# PixelShirtConsole.net
KiCad netlist of a schematic drawn in EAGLE
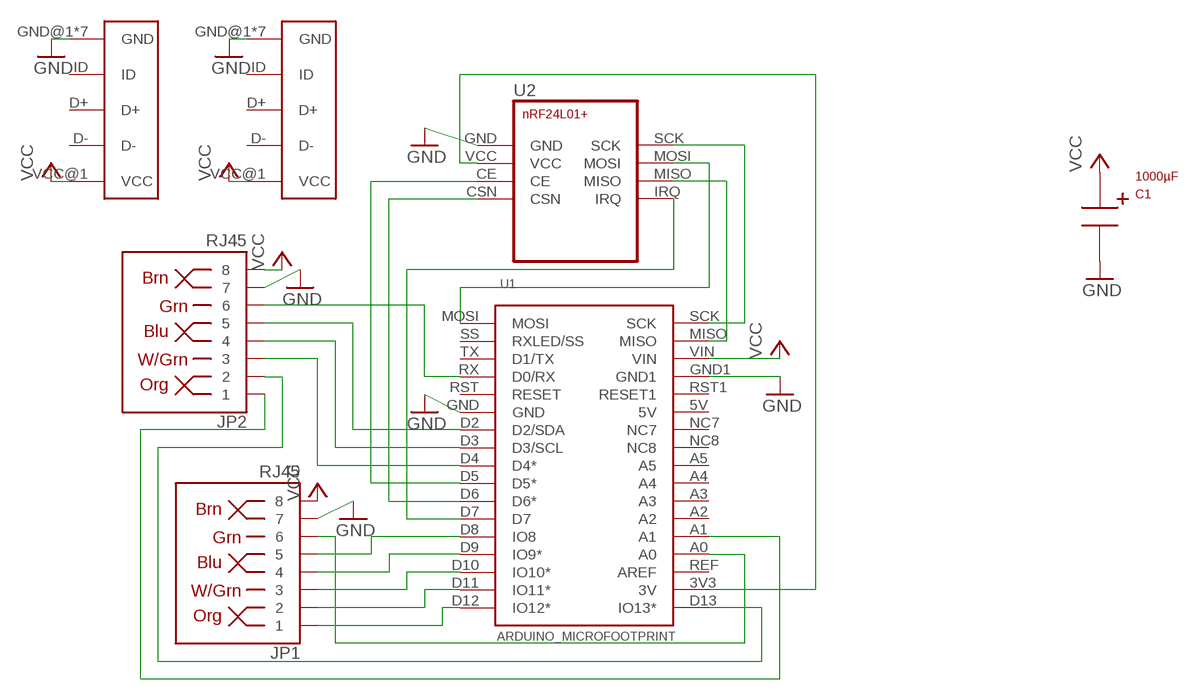
[diagram p0: schematic, sheet 1]

(export (version "E")
  (design (tool "Eeschema 10.0.6"))
  (components
    (comp (ref "C1")
      (value "1000µF")
      (footprint "eagle-import:CAP-CUSTOM")
      (libsource (lib "eagle-import") (part "CAP-CUSTOM"))
    )
    (comp (ref "JP1")
      (value "RJ45")
      (footprint "eagle-import:RJ45-8")
      (libsource (lib "eagle-import") (part "RJ45-8PTH"))
    )
    (comp (ref "JP2")
      (value "RJ45")
      (footprint "eagle-import:RJ45-8")
      (libsource (lib "eagle-import") (part "RJ45-8PTH"))
    )
    (comp (ref "JP3")
      (value "USB-MICRO-B")
      (footprint "eagle-import:USB-MICRO-B")
      (libsource (lib "eagle-import") (part "USB-MICRO-B"))
    )
    (comp (ref "JP4")
      (value "USB-MICRO-B")
      (footprint "eagle-import:USB-MICRO-B")
      (libsource (lib "eagle-import") (part "USB-MICRO-B"))
    )
    (comp (ref "U1")
      (value "ARDUINO_MICROFOOTPRINT")
      (footprint "eagle-import:ARDUINO-MICRO")
      (libsource (lib "eagle-import") (part "ARDUINO_MICROFOOTPRINT"))
    )
    (comp (ref "U2")
      (value "NRF24L01+")
      (footprint "eagle-import:NRF24L01+")
      (libsource (lib "eagle-import") (part "NRF24L01+"))
    )
  )
  (nets
    (net (code "1") (name "GND") (class "Default")
      (node (ref "C1") (pin "GND") (pinfunction "GND_GND") (pintype "bidirectional"))
      (node (ref "JP1") (pin "7") (pinfunction "7_7") (pintype "bidirectional"))
      (node (ref "JP2") (pin "7") (pinfunction "7_7") (pintype "bidirectional"))
      (node (ref "JP3") (pin "GND@1") (pinfunction "GND_GND@1") (pintype "bidirectional"))
      (node (ref "JP3") (pin "GND@2") (pinfunction "GND_GND@2") (pintype "bidirectional"))
      (node (ref "JP3") (pin "GND@3") (pinfunction "GND_GND@3") (pintype "bidirectional"))
      (node (ref "JP3") (pin "GND@5") (pinfunction "GND_GND@5") (pintype "bidirectional"))
      (node (ref "JP3") (pin "GND@6") (pinfunction "GND_GND@6") (pintype "bidirectional"))
      (node (ref "JP3") (pin "GND@7") (pinfunction "GND_GND@7") (pintype "bidirectional"))
      (node (ref "JP3") (pin "GNF@4") (pinfunction "GND_GNF@4") (pintype "bidirectional"))
      (node (ref "JP4") (pin "GND@1") (pinfunction "GND_GND@1") (pintype "bidirectional"))
      (node (ref "JP4") (pin "GND@2") (pinfunction "GND_GND@2") (pintype "bidirectional"))
      (node (ref "JP4") (pin "GND@3") (pinfunction "GND_GND@3") (pintype "bidirectional"))
      (node (ref "JP4") (pin "GND@5") (pinfunction "GND_GND@5") (pintype "bidirectional"))
      (node (ref "JP4") (pin "GND@6") (pinfunction "GND_GND@6") (pintype "bidirectional"))
      (node (ref "JP4") (pin "GND@7") (pinfunction "GND_GND@7") (pintype "bidirectional"))
      (node (ref "JP4") (pin "GNF@4") (pinfunction "GND_GNF@4") (pintype "bidirectional"))
      (node (ref "U1") (pin "GND") (pinfunction "GND_GND") (pintype "bidirectional"))
      (node (ref "U1") (pin "GND1") (pinfunction "GND1_GND1") (pintype "bidirectional"))
      (node (ref "U2") (pin "GND") (pinfunction "GND_GND") (pintype "power_in"))
    )
    (net (code "2") (name "Net-(JP1-Pad6)") (class "Default")
      (node (ref "JP1") (pin "6") (pinfunction "6_6") (pintype "bidirectional"))
      (node (ref "U1") (pin "A0") (pinfunction "A0_A0") (pintype "bidirectional"))
    )
    (net (code "3") (name "Net-(JP2-Pad1)") (class "Default")
      (node (ref "JP2") (pin "1") (pinfunction "1_1") (pintype "bidirectional"))
      (node (ref "U1") (pin "A1") (pinfunction "A1_A1") (pintype "bidirectional"))
    )
    (net (code "4") (name "Net-(U1-3V)") (class "Default")
      (node (ref "U1") (pin "3V3") (pinfunction "3V_3V3") (pintype "bidirectional"))
      (node (ref "U2") (pin "VCC") (pinfunction "VCC_VCC") (pintype "power_in"))
    )
    (net (code "5") (name "Net-(U1-D0{slash}RX)") (class "Default")
      (node (ref "JP2") (pin "6") (pinfunction "6_6") (pintype "bidirectional"))
      (node (ref "U1") (pin "RX") (pinfunction "D0/RX_RX") (pintype "bidirectional"))
    )
    (net (code "6") (name "Net-(U1-D2{slash}SDA)") (class "Default")
      (node (ref "JP2") (pin "5") (pinfunction "5_5") (pintype "bidirectional"))
      (node (ref "U1") (pin "D2") (pinfunction "D2/SDA_D2") (pintype "bidirectional"))
    )
    (net (code "7") (name "Net-(U1-D3{slash}SCL)") (class "Default")
      (node (ref "JP2") (pin "4") (pinfunction "4_4") (pintype "bidirectional"))
      (node (ref "U1") (pin "D3") (pinfunction "D3/SCL_D3") (pintype "bidirectional"))
    )
    (net (code "8") (name "Net-(U1-D4*)") (class "Default")
      (node (ref "JP2") (pin "3") (pinfunction "3_3") (pintype "bidirectional"))
      (node (ref "U1") (pin "D4") (pinfunction "D4*_D4") (pintype "bidirectional"))
    )
    (net (code "9") (name "Net-(U1-D5*)") (class "Default")
      (node (ref "U1") (pin "D5") (pinfunction "D5*_D5") (pintype "bidirectional"))
      (node (ref "U2") (pin "CE") (pinfunction "CE_CE") (pintype "bidirectional"))
    )
    (net (code "10") (name "Net-(U1-D6*)") (class "Default")
      (node (ref "U1") (pin "D6") (pinfunction "D6*_D6") (pintype "bidirectional"))
      (node (ref "U2") (pin "CSN") (pinfunction "CSN_CSN") (pintype "bidirectional"))
    )
    (net (code "11") (name "Net-(U1-IO8)") (class "Default")
      (node (ref "JP1") (pin "5") (pinfunction "5_5") (pintype "bidirectional"))
      (node (ref "U1") (pin "D8") (pinfunction "IO8_D8") (pintype "bidirectional"))
    )
    (net (code "12") (name "Net-(U1-IO9*)") (class "Default")
      (node (ref "JP1") (pin "4") (pinfunction "4_4") (pintype "bidirectional"))
      (node (ref "U1") (pin "D9") (pinfunction "IO9*_D9") (pintype "bidirectional"))
    )
    (net (code "13") (name "Net-(U1-IO10*)") (class "Default")
      (node (ref "JP1") (pin "3") (pinfunction "3_3") (pintype "bidirectional"))
      (node (ref "U1") (pin "D10") (pinfunction "IO10*_D10") (pintype "bidirectional"))
    )
    (net (code "14") (name "Net-(U1-IO11*)") (class "Default")
      (node (ref "JP1") (pin "2") (pinfunction "2_2") (pintype "bidirectional"))
      (node (ref "U1") (pin "D11") (pinfunction "IO11*_D11") (pintype "bidirectional"))
    )
    (net (code "15") (name "Net-(U1-IO12*)") (class "Default")
      (node (ref "JP1") (pin "1") (pinfunction "1_1") (pintype "bidirectional"))
      (node (ref "U1") (pin "D12") (pinfunction "IO12*_D12") (pintype "bidirectional"))
    )
    (net (code "16") (name "Net-(U1-IO13*)") (class "Default")
      (node (ref "JP2") (pin "2") (pinfunction "2_2") (pintype "bidirectional"))
      (node (ref "U1") (pin "D13") (pinfunction "IO13*_D13") (pintype "bidirectional"))
    )
    (net (code "17") (name "Net-(U1-PadD7)") (class "Default")
      (node (ref "U1") (pin "D7") (pinfunction "D7_D7") (pintype "bidirectional"))
      (node (ref "U2") (pin "IRQ") (pinfunction "IRQ_IRQ") (pintype "bidirectional"))
    )
    (net (code "18") (name "Net-(U1-PadMISO)") (class "Default")
      (node (ref "U1") (pin "MISO") (pinfunction "MISO_MISO") (pintype "bidirectional"))
      (node (ref "U2") (pin "MISO") (pinfunction "MISO_MISO") (pintype "bidirectional"))
    )
    (net (code "19") (name "Net-(U1-PadMOSI)") (class "Default")
      (node (ref "U1") (pin "MOSI") (pinfunction "MOSI_MOSI") (pintype "bidirectional"))
      (node (ref "U2") (pin "MOSI") (pinfunction "MOSI_MOSI") (pintype "bidirectional"))
    )
    (net (code "20") (name "Net-(U1-PadSCK)") (class "Default")
      (node (ref "U1") (pin "SCK") (pinfunction "SCK_SCK") (pintype "bidirectional"))
      (node (ref "U2") (pin "SCK") (pinfunction "SCK_SCK") (pintype "bidirectional"))
    )
    (net (code "21") (name "VCC") (class "Default")
      (node (ref "C1") (pin "VCC") (pinfunction "VCC_VCC") (pintype "bidirectional"))
      (node (ref "JP1") (pin "8") (pinfunction "8_8") (pintype "bidirectional"))
      (node (ref "JP2") (pin "8") (pinfunction "8_8") (pintype "bidirectional"))
      (node (ref "JP3") (pin "VCC@1") (pinfunction "VCC_VCC@1") (pintype "bidirectional"))
      (node (ref "JP4") (pin "VCC@1") (pinfunction "VCC_VCC@1") (pintype "bidirectional"))
      (node (ref "U1") (pin "VIN") (pinfunction "VIN_VIN") (pintype "bidirectional"))
    )
    (net (code "22") (name "unconnected-(JP3-PadD+)") (class "Default")
      (node (ref "JP3") (pin "D+") (pinfunction "D+_D+") (pintype "bidirectional"))
    )
    (net (code "23") (name "unconnected-(JP3-PadD-)") (class "Default")
      (node (ref "JP3") (pin "D-") (pinfunction "D-_D-") (pintype "bidirectional"))
    )
    (net (code "24") (name "unconnected-(JP3-PadID)") (class "Default")
      (node (ref "JP3") (pin "ID") (pinfunction "ID_ID") (pintype "bidirectional"))
    )
    (net (code "25") (name "unconnected-(JP4-PadD+)") (class "Default")
      (node (ref "JP4") (pin "D+") (pinfunction "D+_D+") (pintype "bidirectional"))
    )
    (net (code "26") (name "unconnected-(JP4-PadD-)") (class "Default")
      (node (ref "JP4") (pin "D-") (pinfunction "D-_D-") (pintype "bidirectional"))
    )
    (net (code "27") (name "unconnected-(JP4-PadID)") (class "Default")
      (node (ref "JP4") (pin "ID") (pinfunction "ID_ID") (pintype "bidirectional"))
    )
    (net (code "28") (name "unconnected-(U1-AREF-PadREF)") (class "Default")
      (node (ref "U1") (pin "REF") (pinfunction "AREF_REF") (pintype "bidirectional"))
    )
    (net (code "29") (name "unconnected-(U1-D1{slash}TX-PadTX)") (class "Default")
      (node (ref "U1") (pin "TX") (pinfunction "D1/TX_TX") (pintype "bidirectional"))
    )
    (net (code "30") (name "unconnected-(U1-Pad5V)") (class "Default")
      (node (ref "U1") (pin "5V") (pinfunction "5V_5V") (pintype "bidirectional"))
    )
    (net (code "31") (name "unconnected-(U1-PadA2)") (class "Default")
      (node (ref "U1") (pin "A2") (pinfunction "A2_A2") (pintype "bidirectional"))
    )
    (net (code "32") (name "unconnected-(U1-PadA3)") (class "Default")
      (node (ref "U1") (pin "A3") (pinfunction "A3_A3") (pintype "bidirectional"))
    )
    (net (code "33") (name "unconnected-(U1-PadA4)") (class "Default")
      (node (ref "U1") (pin "A4") (pinfunction "A4_A4") (pintype "bidirectional"))
    )
    (net (code "34") (name "unconnected-(U1-PadA5)") (class "Default")
      (node (ref "U1") (pin "A5") (pinfunction "A5_A5") (pintype "bidirectional"))
    )
    (net (code "35") (name "unconnected-(U1-PadNC7)") (class "Default")
      (node (ref "U1") (pin "NC7") (pinfunction "NC7_NC7") (pintype "bidirectional"))
    )
    (net (code "36") (name "unconnected-(U1-PadNC8)") (class "Default")
      (node (ref "U1") (pin "NC8") (pinfunction "NC8_NC8") (pintype "bidirectional"))
    )
    (net (code "37") (name "unconnected-(U1-RESET-PadRST)") (class "Default")
      (node (ref "U1") (pin "RST") (pinfunction "RESET_RST") (pintype "bidirectional"))
    )
    (net (code "38") (name "unconnected-(U1-RESET1-PadRST1)") (class "Default")
      (node (ref "U1") (pin "RST1") (pinfunction "RESET1_RST1") (pintype "bidirectional"))
    )
    (net (code "39") (name "unconnected-(U1-RXLED{slash}SS-PadSS)") (class "Default")
      (node (ref "U1") (pin "SS") (pinfunction "RXLED/SS_SS") (pintype "bidirectional"))
    )
  )
)
